# M7102.net
KiCad netlist of a schematic drawn in EAGLE
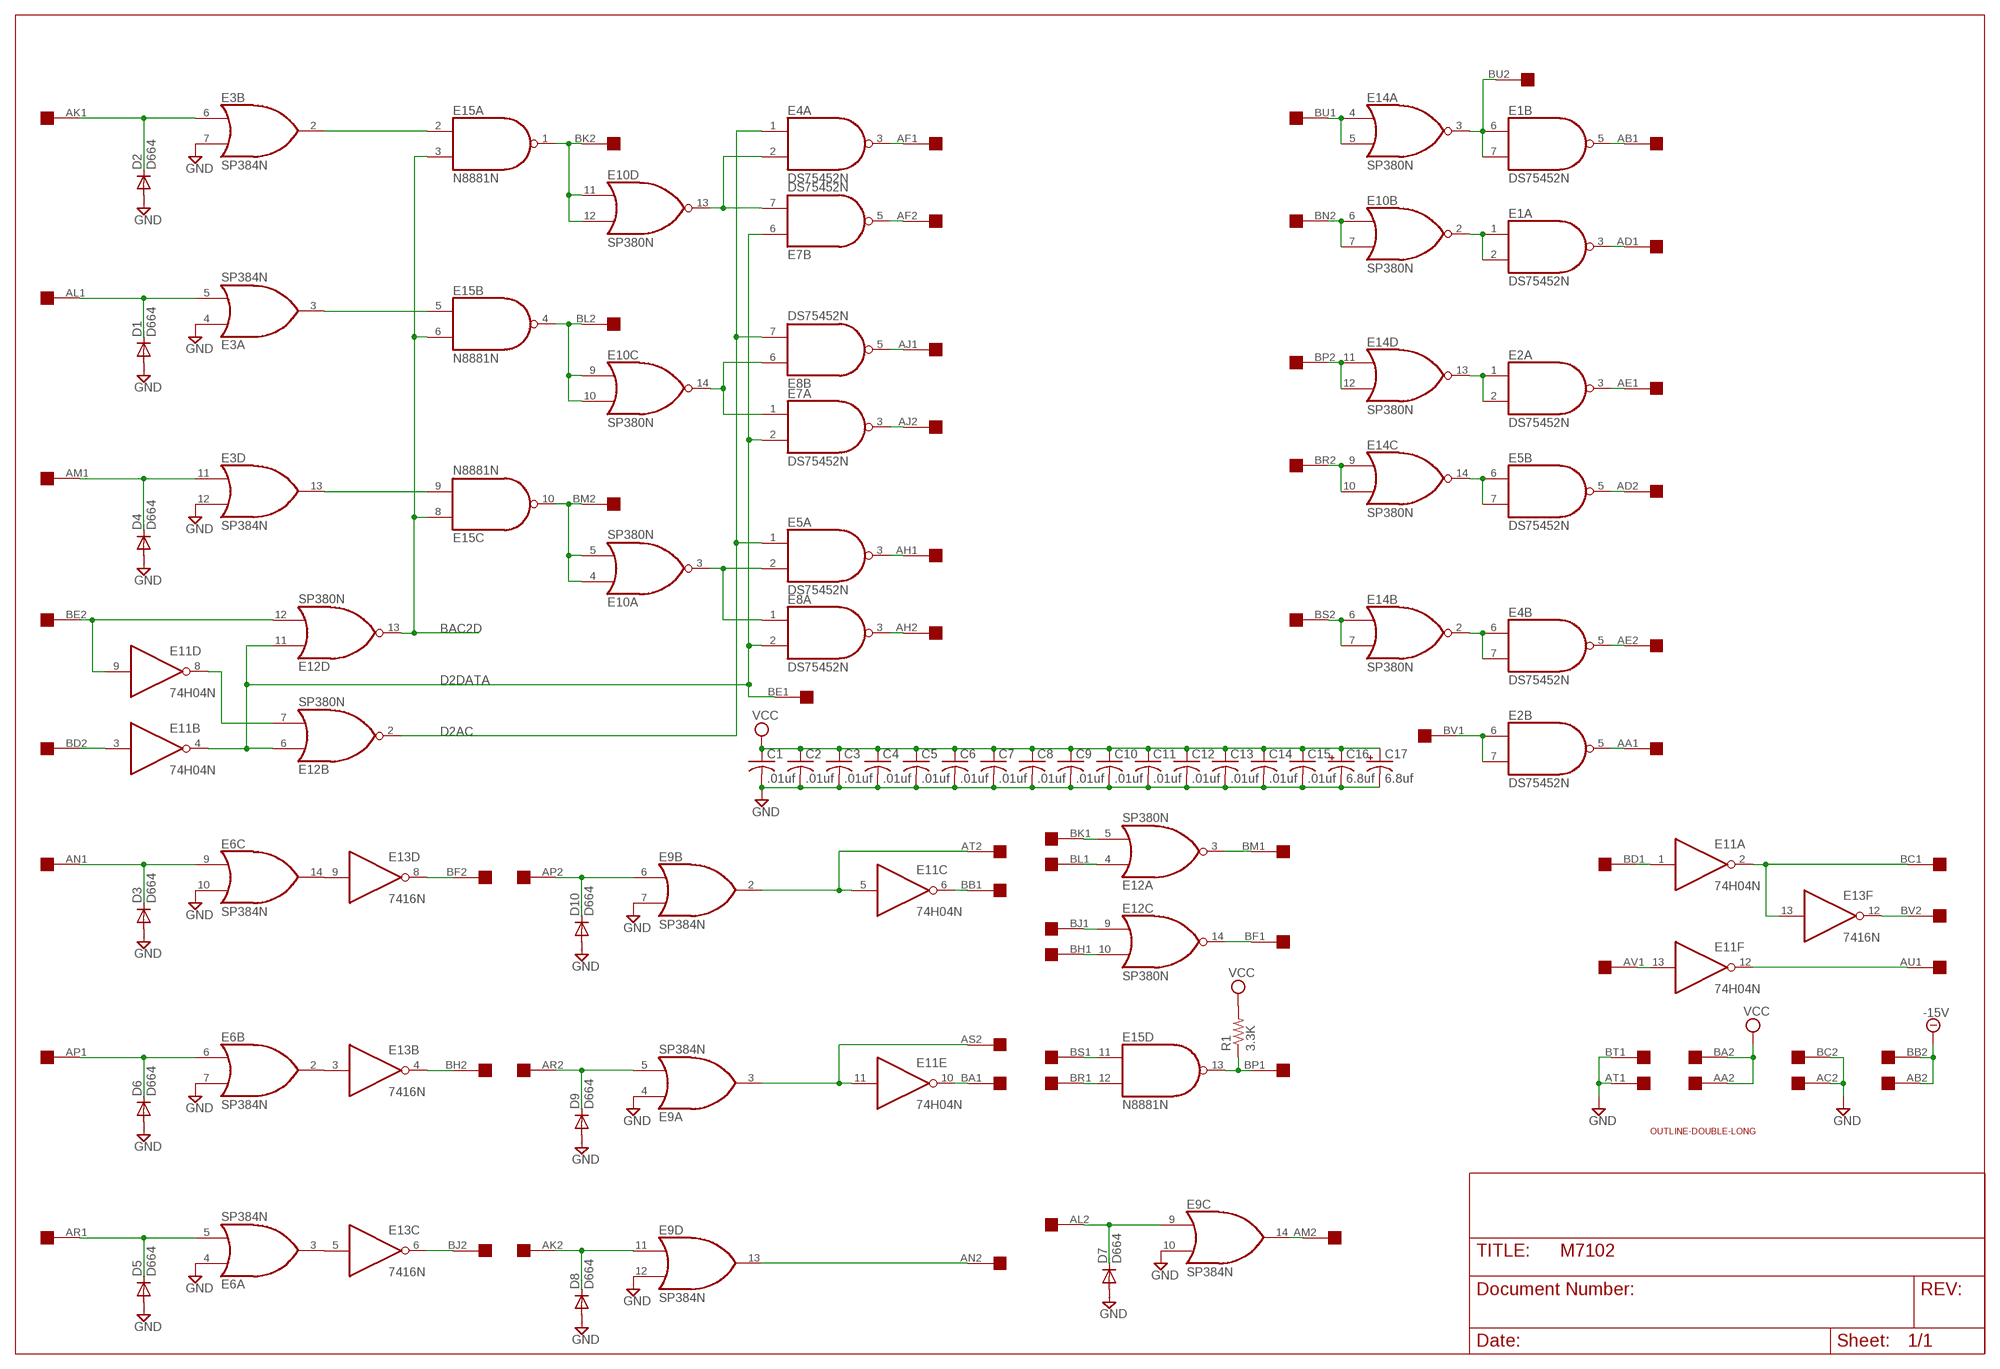
[diagram p0: schematic, sheet 1]

(export (version "E")
  (design (tool "Eeschema 10.0.6"))
  (components
    (comp (ref "C1")
      (value ".01uf")
      (footprint "eagle-import:C050-025X075")
      (libsource (lib "eagle-import") (part "C-US050-025X075"))
    )
    (comp (ref "C2")
      (value ".01uf")
      (footprint "eagle-import:C050-025X075")
      (libsource (lib "eagle-import") (part "C-US050-025X075"))
    )
    (comp (ref "C3")
      (value ".01uf")
      (footprint "eagle-import:C050-025X075")
      (libsource (lib "eagle-import") (part "C-US050-025X075"))
    )
    (comp (ref "C4")
      (value ".01uf")
      (footprint "eagle-import:C050-025X075")
      (libsource (lib "eagle-import") (part "C-US050-025X075"))
    )
    (comp (ref "C5")
      (value ".01uf")
      (footprint "eagle-import:C050-025X075")
      (libsource (lib "eagle-import") (part "C-US050-025X075"))
    )
    (comp (ref "C6")
      (value ".01uf")
      (footprint "eagle-import:C050-025X075")
      (libsource (lib "eagle-import") (part "C-US050-025X075"))
    )
    (comp (ref "C7")
      (value ".01uf")
      (footprint "eagle-import:C050-025X075")
      (libsource (lib "eagle-import") (part "C-US050-025X075"))
    )
    (comp (ref "C8")
      (value ".01uf")
      (footprint "eagle-import:C050-025X075")
      (libsource (lib "eagle-import") (part "C-US050-025X075"))
    )
    (comp (ref "C9")
      (value ".01uf")
      (footprint "eagle-import:C050-025X075")
      (libsource (lib "eagle-import") (part "C-US050-025X075"))
    )
    (comp (ref "C10")
      (value ".01uf")
      (footprint "eagle-import:C050-025X075")
      (libsource (lib "eagle-import") (part "C-US050-025X075"))
    )
    (comp (ref "C11")
      (value ".01uf")
      (footprint "eagle-import:C050-025X075")
      (libsource (lib "eagle-import") (part "C-US050-025X075"))
    )
    (comp (ref "C12")
      (value ".01uf")
      (footprint "eagle-import:C050-025X075")
      (libsource (lib "eagle-import") (part "C-US050-025X075"))
    )
    (comp (ref "C13")
      (value ".01uf")
      (footprint "eagle-import:C050-025X075")
      (libsource (lib "eagle-import") (part "C-US050-025X075"))
    )
    (comp (ref "C14")
      (value ".01uf")
      (footprint "eagle-import:C050-025X075")
      (libsource (lib "eagle-import") (part "C-US050-025X075"))
    )
    (comp (ref "C15")
      (value ".01uf")
      (footprint "eagle-import:C050-025X075")
      (libsource (lib "eagle-import") (part "C-US050-025X075"))
    )
    (comp (ref "C16")
      (value "6.8uf")
      (footprint "eagle-import:E15-5")
      (libsource (lib "eagle-import") (part "CPOL-USE15-5AXIAL"))
    )
    (comp (ref "C17")
      (value "6.8uf")
      (footprint "eagle-import:E15-5")
      (libsource (lib "eagle-import") (part "CPOL-USE15-5AXIAL"))
    )
    (comp (ref "D1")
      (value "D664")
      (footprint "eagle-import:DO35-10")
      (libsource (lib "eagle-import") (part "1N4148DO35-10"))
    )
    (comp (ref "D2")
      (value "D664")
      (footprint "eagle-import:DO35-10")
      (libsource (lib "eagle-import") (part "1N4148DO35-10"))
    )
    (comp (ref "D3")
      (value "D664")
      (footprint "eagle-import:DO35-10")
      (libsource (lib "eagle-import") (part "1N4148DO35-10"))
    )
    (comp (ref "D4")
      (value "D664")
      (footprint "eagle-import:DO35-10")
      (libsource (lib "eagle-import") (part "1N4148DO35-10"))
    )
    (comp (ref "D5")
      (value "D664")
      (footprint "eagle-import:DO35-10")
      (libsource (lib "eagle-import") (part "1N4148DO35-10"))
    )
    (comp (ref "D6")
      (value "D664")
      (footprint "eagle-import:DO35-10")
      (libsource (lib "eagle-import") (part "1N4148DO35-10"))
    )
    (comp (ref "D7")
      (value "D664")
      (footprint "eagle-import:DO35-10")
      (libsource (lib "eagle-import") (part "1N4148DO35-10"))
    )
    (comp (ref "D8")
      (value "D664")
      (footprint "eagle-import:DO35-10")
      (libsource (lib "eagle-import") (part "1N4148DO35-10"))
    )
    (comp (ref "D9")
      (value "D664")
      (footprint "eagle-import:DO35-10")
      (libsource (lib "eagle-import") (part "1N4148DO35-10"))
    )
    (comp (ref "D10")
      (value "D664")
      (footprint "eagle-import:DO35-10")
      (libsource (lib "eagle-import") (part "1N4148DO35-10"))
    )
    (comp (ref "E1")
      (value "DS75452N")
      (footprint "eagle-import:DIL08")
      (libsource (lib "eagle-import") (part "DS75452N"))
    )
    (comp (ref "E2")
      (value "DS75452N")
      (footprint "eagle-import:DIL08")
      (libsource (lib "eagle-import") (part "DS75452N"))
    )
    (comp (ref "E3")
      (value "SP384N")
      (footprint "eagle-import:DIL14")
      (libsource (lib "eagle-import") (part "SP384N"))
    )
    (comp (ref "E4")
      (value "DS75452N")
      (footprint "eagle-import:DIL08")
      (libsource (lib "eagle-import") (part "DS75452N"))
    )
    (comp (ref "E5")
      (value "DS75452N")
      (footprint "eagle-import:DIL08")
      (libsource (lib "eagle-import") (part "DS75452N"))
    )
    (comp (ref "E6")
      (value "SP384N")
      (footprint "eagle-import:DIL14")
      (libsource (lib "eagle-import") (part "SP384N"))
    )
    (comp (ref "E7")
      (value "DS75452N")
      (footprint "eagle-import:DIL08")
      (libsource (lib "eagle-import") (part "DS75452N"))
    )
    (comp (ref "E8")
      (value "DS75452N")
      (footprint "eagle-import:DIL08")
      (libsource (lib "eagle-import") (part "DS75452N"))
    )
    (comp (ref "E9")
      (value "SP384N")
      (footprint "eagle-import:DIL14")
      (libsource (lib "eagle-import") (part "SP384N"))
    )
    (comp (ref "E10")
      (value "SP380N")
      (footprint "eagle-import:DIL14")
      (libsource (lib "eagle-import") (part "SP380N"))
    )
    (comp (ref "E11")
      (value "74H04N")
      (footprint "eagle-import:DIL14")
      (libsource (lib "eagle-import") (part "7404N"))
    )
    (comp (ref "E12")
      (value "SP380N")
      (footprint "eagle-import:DIL14")
      (libsource (lib "eagle-import") (part "SP380N"))
    )
    (comp (ref "E13")
      (value "7416N")
      (footprint "eagle-import:DIL14")
      (libsource (lib "eagle-import") (part "7416N"))
    )
    (comp (ref "E14")
      (value "SP380N")
      (footprint "eagle-import:DIL14")
      (libsource (lib "eagle-import") (part "SP380N"))
    )
    (comp (ref "E15")
      (value "N8881N")
      (footprint "eagle-import:DIL14")
      (libsource (lib "eagle-import") (part "N8881N"))
    )
    (comp (ref "EDGE")
      (value "DOUBLE")
      (footprint "eagle-import:EDGE-CON4")
      (libsource (lib "eagle-import") (part "DOUBLE"))
    )
    (comp (ref "R1")
      (value "3.3K")
      (footprint "eagle-import:0207_10")
      (libsource (lib "eagle-import") (part "R-US_0207/10"))
    )
    (comp (ref "U$3")
      (value "OUTLINE-DOUBLE-LONG")
      (footprint "eagle-import:DOUBLE-LONG")
      (libsource (lib "eagle-import") (part "OUTLINE-DOUBLE-LONG"))
    )
  )
  (nets
    (net (code "1") (name "-15V") (class "Default")
      (node (ref "EDGE") (pin "AB2") (pinfunction "1_AB2") (pintype "bidirectional"))
      (node (ref "EDGE") (pin "BB2") (pinfunction "1_BB2") (pintype "bidirectional"))
    )
    (net (code "2") (name "/BAC2D") (class "Default")
      (node (ref "E12") (pin "13") (pinfunction "O_13") (pintype "output"))
      (node (ref "E15") (pin "3") (pinfunction "I1_3") (pintype "input"))
      (node (ref "E15") (pin "6") (pinfunction "I1_6") (pintype "input"))
      (node (ref "E15") (pin "8") (pinfunction "I0_8") (pintype "input"))
    )
    (net (code "3") (name "/D2AC") (class "Default")
      (node (ref "E12") (pin "2") (pinfunction "O_2") (pintype "output"))
      (node (ref "E4") (pin "1") (pinfunction "I0_1") (pintype "input"))
      (node (ref "E5") (pin "1") (pinfunction "I0_1") (pintype "input"))
      (node (ref "E8") (pin "7") (pinfunction "I1_7") (pintype "input"))
    )
    (net (code "4") (name "/D2DATA") (class "Default")
      (node (ref "E11") (pin "4") (pinfunction "O_4") (pintype "output"))
      (node (ref "E12") (pin "11") (pinfunction "I0_11") (pintype "input"))
      (node (ref "E12") (pin "6") (pinfunction "I0_6") (pintype "input"))
      (node (ref "E7") (pin "2") (pinfunction "I1_2") (pintype "input"))
      (node (ref "E7") (pin "6") (pinfunction "I0_6") (pintype "input"))
      (node (ref "E8") (pin "2") (pinfunction "I1_2") (pintype "input"))
      (node (ref "EDGE") (pin "BE1") (pinfunction "1_BE1") (pintype "bidirectional"))
    )
    (net (code "5") (name "GND") (class "Default")
      (node (ref "C1") (pin "2") (pinfunction "2_2") (pintype "passive"))
      (node (ref "C10") (pin "2") (pinfunction "2_2") (pintype "passive"))
      (node (ref "C11") (pin "2") (pinfunction "2_2") (pintype "passive"))
      (node (ref "C12") (pin "2") (pinfunction "2_2") (pintype "passive"))
      (node (ref "C13") (pin "2") (pinfunction "2_2") (pintype "passive"))
      (node (ref "C14") (pin "2") (pinfunction "2_2") (pintype "passive"))
      (node (ref "C15") (pin "2") (pinfunction "2_2") (pintype "passive"))
      (node (ref "C16") (pin "-") (pinfunction "-_-") (pintype "passive"))
      (node (ref "C17") (pin "-") (pinfunction "-_-") (pintype "passive"))
      (node (ref "C2") (pin "2") (pinfunction "2_2") (pintype "passive"))
      (node (ref "C3") (pin "2") (pinfunction "2_2") (pintype "passive"))
      (node (ref "C4") (pin "2") (pinfunction "2_2") (pintype "passive"))
      (node (ref "C5") (pin "2") (pinfunction "2_2") (pintype "passive"))
      (node (ref "C6") (pin "2") (pinfunction "2_2") (pintype "passive"))
      (node (ref "C7") (pin "2") (pinfunction "2_2") (pintype "passive"))
      (node (ref "C8") (pin "2") (pinfunction "2_2") (pintype "passive"))
      (node (ref "C9") (pin "2") (pinfunction "2_2") (pintype "passive"))
      (node (ref "D1") (pin "A") (pinfunction "A_A") (pintype "passive"))
      (node (ref "D10") (pin "A") (pinfunction "A_A") (pintype "passive"))
      (node (ref "D2") (pin "A") (pinfunction "A_A") (pintype "passive"))
      (node (ref "D3") (pin "A") (pinfunction "A_A") (pintype "passive"))
      (node (ref "D4") (pin "A") (pinfunction "A_A") (pintype "passive"))
      (node (ref "D5") (pin "A") (pinfunction "A_A") (pintype "passive"))
      (node (ref "D6") (pin "A") (pinfunction "A_A") (pintype "passive"))
      (node (ref "D7") (pin "A") (pinfunction "A_A") (pintype "passive"))
      (node (ref "D8") (pin "A") (pinfunction "A_A") (pintype "passive"))
      (node (ref "D9") (pin "A") (pinfunction "A_A") (pintype "passive"))
      (node (ref "E3") (pin "12") (pinfunction "I1_12") (pintype "input"))
      (node (ref "E3") (pin "4") (pinfunction "I0_4") (pintype "input"))
      (node (ref "E3") (pin "7") (pinfunction "I1_7") (pintype "input"))
      (node (ref "E6") (pin "10") (pinfunction "I1_10") (pintype "input"))
      (node (ref "E6") (pin "4") (pinfunction "I0_4") (pintype "input"))
      (node (ref "E6") (pin "7") (pinfunction "I1_7") (pintype "input"))
      (node (ref "E9") (pin "10") (pinfunction "I1_10") (pintype "input"))
      (node (ref "E9") (pin "12") (pinfunction "I1_12") (pintype "input"))
      (node (ref "E9") (pin "4") (pinfunction "I0_4") (pintype "input"))
      (node (ref "E9") (pin "7") (pinfunction "I1_7") (pintype "input"))
      (node (ref "EDGE") (pin "AC2") (pinfunction "1_AC2") (pintype "bidirectional"))
      (node (ref "EDGE") (pin "AT1") (pinfunction "1_AT1") (pintype "bidirectional"))
      (node (ref "EDGE") (pin "BC2") (pinfunction "1_BC2") (pintype "bidirectional"))
      (node (ref "EDGE") (pin "BT1") (pinfunction "1_BT1") (pintype "bidirectional"))
    )
    (net (code "6") (name "Net-(E1A-O)") (class "Default")
      (node (ref "E1") (pin "3") (pinfunction "O_3") (pintype "open_collector"))
      (node (ref "EDGE") (pin "AD1") (pinfunction "1_AD1") (pintype "bidirectional"))
    )
    (net (code "7") (name "Net-(E1B-O)") (class "Default")
      (node (ref "E1") (pin "5") (pinfunction "O_5") (pintype "open_collector"))
      (node (ref "EDGE") (pin "AB1") (pinfunction "1_AB1") (pintype "bidirectional"))
    )
    (net (code "8") (name "Net-(E2A-O)") (class "Default")
      (node (ref "E2") (pin "3") (pinfunction "O_3") (pintype "open_collector"))
      (node (ref "EDGE") (pin "AE1") (pinfunction "1_AE1") (pintype "bidirectional"))
    )
    (net (code "9") (name "Net-(E2B-I0)") (class "Default")
      (node (ref "E2") (pin "6") (pinfunction "I0_6") (pintype "input"))
      (node (ref "E2") (pin "7") (pinfunction "I1_7") (pintype "input"))
      (node (ref "EDGE") (pin "BV1") (pinfunction "1_BV1") (pintype "bidirectional"))
    )
    (net (code "10") (name "Net-(E2B-O)") (class "Default")
      (node (ref "E2") (pin "5") (pinfunction "O_5") (pintype "open_collector"))
      (node (ref "EDGE") (pin "AA1") (pinfunction "1_AA1") (pintype "bidirectional"))
    )
    (net (code "11") (name "Net-(E3A-I1)") (class "Default")
      (node (ref "D1") (pin "C") (pinfunction "C_C") (pintype "passive"))
      (node (ref "E3") (pin "5") (pinfunction "I1_5") (pintype "input"))
      (node (ref "EDGE") (pin "AL1") (pinfunction "1_AL1") (pintype "bidirectional"))
    )
    (net (code "12") (name "Net-(E3B-I0)") (class "Default")
      (node (ref "D2") (pin "C") (pinfunction "C_C") (pintype "passive"))
      (node (ref "E3") (pin "6") (pinfunction "I0_6") (pintype "input"))
      (node (ref "EDGE") (pin "AK1") (pinfunction "1_AK1") (pintype "bidirectional"))
    )
    (net (code "13") (name "Net-(E3D-I0)") (class "Default")
      (node (ref "D4") (pin "C") (pinfunction "C_C") (pintype "passive"))
      (node (ref "E3") (pin "11") (pinfunction "I0_11") (pintype "input"))
      (node (ref "EDGE") (pin "AM1") (pinfunction "1_AM1") (pintype "bidirectional"))
    )
    (net (code "14") (name "Net-(E4A-O)") (class "Default")
      (node (ref "E4") (pin "3") (pinfunction "O_3") (pintype "open_collector"))
      (node (ref "EDGE") (pin "AF1") (pinfunction "1_AF1") (pintype "bidirectional"))
    )
    (net (code "15") (name "Net-(E4B-O)") (class "Default")
      (node (ref "E4") (pin "5") (pinfunction "O_5") (pintype "open_collector"))
      (node (ref "EDGE") (pin "AE2") (pinfunction "1_AE2") (pintype "bidirectional"))
    )
    (net (code "16") (name "Net-(E5A-O)") (class "Default")
      (node (ref "E5") (pin "3") (pinfunction "O_3") (pintype "open_collector"))
      (node (ref "EDGE") (pin "AH1") (pinfunction "1_AH1") (pintype "bidirectional"))
    )
    (net (code "17") (name "Net-(E5B-O)") (class "Default")
      (node (ref "E5") (pin "5") (pinfunction "O_5") (pintype "open_collector"))
      (node (ref "EDGE") (pin "AD2") (pinfunction "1_AD2") (pintype "bidirectional"))
    )
    (net (code "18") (name "Net-(E6A-I1)") (class "Default")
      (node (ref "D5") (pin "C") (pinfunction "C_C") (pintype "passive"))
      (node (ref "E6") (pin "5") (pinfunction "I1_5") (pintype "input"))
      (node (ref "EDGE") (pin "AR1") (pinfunction "1_AR1") (pintype "bidirectional"))
    )
    (net (code "19") (name "Net-(E6B-I0)") (class "Default")
      (node (ref "D6") (pin "C") (pinfunction "C_C") (pintype "passive"))
      (node (ref "E6") (pin "6") (pinfunction "I0_6") (pintype "input"))
      (node (ref "EDGE") (pin "AP1") (pinfunction "1_AP1") (pintype "bidirectional"))
    )
    (net (code "20") (name "Net-(E6C-I0)") (class "Default")
      (node (ref "D3") (pin "C") (pinfunction "C_C") (pintype "passive"))
      (node (ref "E6") (pin "9") (pinfunction "I0_9") (pintype "input"))
      (node (ref "EDGE") (pin "AN1") (pinfunction "1_AN1") (pintype "bidirectional"))
    )
    (net (code "21") (name "Net-(E7A-O)") (class "Default")
      (node (ref "E7") (pin "3") (pinfunction "O_3") (pintype "open_collector"))
      (node (ref "EDGE") (pin "AJ2") (pinfunction "1_AJ2") (pintype "bidirectional"))
    )
    (net (code "22") (name "Net-(E7B-O)") (class "Default")
      (node (ref "E7") (pin "5") (pinfunction "O_5") (pintype "open_collector"))
      (node (ref "EDGE") (pin "AF2") (pinfunction "1_AF2") (pintype "bidirectional"))
    )
    (net (code "23") (name "Net-(E8A-O)") (class "Default")
      (node (ref "E8") (pin "3") (pinfunction "O_3") (pintype "open_collector"))
      (node (ref "EDGE") (pin "AH2") (pinfunction "1_AH2") (pintype "bidirectional"))
    )
    (net (code "24") (name "Net-(E8B-O)") (class "Default")
      (node (ref "E8") (pin "5") (pinfunction "O_5") (pintype "open_collector"))
      (node (ref "EDGE") (pin "AJ1") (pinfunction "1_AJ1") (pintype "bidirectional"))
    )
    (net (code "25") (name "Net-(E9A-I1)") (class "Default")
      (node (ref "D9") (pin "C") (pinfunction "C_C") (pintype "passive"))
      (node (ref "E9") (pin "5") (pinfunction "I1_5") (pintype "input"))
      (node (ref "EDGE") (pin "AR2") (pinfunction "1_AR2") (pintype "bidirectional"))
    )
    (net (code "26") (name "Net-(E9B-I0)") (class "Default")
      (node (ref "D10") (pin "C") (pinfunction "C_C") (pintype "passive"))
      (node (ref "E9") (pin "6") (pinfunction "I0_6") (pintype "input"))
      (node (ref "EDGE") (pin "AP2") (pinfunction "1_AP2") (pintype "bidirectional"))
    )
    (net (code "27") (name "Net-(E9C-I0)") (class "Default")
      (node (ref "D7") (pin "C") (pinfunction "C_C") (pintype "passive"))
      (node (ref "E9") (pin "9") (pinfunction "I0_9") (pintype "input"))
      (node (ref "EDGE") (pin "AL2") (pinfunction "1_AL2") (pintype "bidirectional"))
    )
    (net (code "28") (name "Net-(E9C-O)") (class "Default")
      (node (ref "E9") (pin "14") (pinfunction "O_14") (pintype "output"))
      (node (ref "EDGE") (pin "AM2") (pinfunction "1_AM2") (pintype "bidirectional"))
    )
    (net (code "29") (name "Net-(E9D-I0)") (class "Default")
      (node (ref "D8") (pin "C") (pinfunction "C_C") (pintype "passive"))
      (node (ref "E9") (pin "11") (pinfunction "I0_11") (pintype "input"))
      (node (ref "EDGE") (pin "AK2") (pinfunction "1_AK2") (pintype "bidirectional"))
    )
    (net (code "30") (name "Net-(E9D-O)") (class "Default")
      (node (ref "E9") (pin "13") (pinfunction "O_13") (pintype "output"))
      (node (ref "EDGE") (pin "AN2") (pinfunction "1_AN2") (pintype "bidirectional"))
    )
    (net (code "31") (name "Net-(E10A-I0)") (class "Default")
      (node (ref "E10") (pin "4") (pinfunction "I0_4") (pintype "input"))
      (node (ref "E10") (pin "5") (pinfunction "I1_5") (pintype "input"))
      (node (ref "E15") (pin "10") (pinfunction "O_10") (pintype "open_collector"))
      (node (ref "EDGE") (pin "BM2") (pinfunction "1_BM2") (pintype "bidirectional"))
    )
    (net (code "32") (name "Net-(E10A-O)") (class "Default")
      (node (ref "E10") (pin "3") (pinfunction "O_3") (pintype "output"))
      (node (ref "E5") (pin "2") (pinfunction "I1_2") (pintype "input"))
      (node (ref "E8") (pin "1") (pinfunction "I0_1") (pintype "input"))
    )
    (net (code "33") (name "Net-(E10B-I0)") (class "Default")
      (node (ref "E10") (pin "6") (pinfunction "I0_6") (pintype "input"))
      (node (ref "E10") (pin "7") (pinfunction "I1_7") (pintype "input"))
      (node (ref "EDGE") (pin "BN2") (pinfunction "1_BN2") (pintype "bidirectional"))
    )
    (net (code "34") (name "Net-(E10B-O)") (class "Default")
      (node (ref "E1") (pin "1") (pinfunction "I0_1") (pintype "input"))
      (node (ref "E1") (pin "2") (pinfunction "I1_2") (pintype "input"))
      (node (ref "E10") (pin "2") (pinfunction "O_2") (pintype "output"))
    )
    (net (code "35") (name "Net-(E10C-I0)") (class "Default")
      (node (ref "E10") (pin "10") (pinfunction "I1_10") (pintype "input"))
      (node (ref "E10") (pin "9") (pinfunction "I0_9") (pintype "input"))
      (node (ref "E15") (pin "4") (pinfunction "O_4") (pintype "open_collector"))
      (node (ref "EDGE") (pin "BL2") (pinfunction "1_BL2") (pintype "bidirectional"))
    )
    (net (code "36") (name "Net-(E10C-O)") (class "Default")
      (node (ref "E10") (pin "14") (pinfunction "O_14") (pintype "output"))
      (node (ref "E7") (pin "1") (pinfunction "I0_1") (pintype "input"))
      (node (ref "E8") (pin "6") (pinfunction "I0_6") (pintype "input"))
    )
    (net (code "37") (name "Net-(E10D-I0)") (class "Default")
      (node (ref "E10") (pin "11") (pinfunction "I0_11") (pintype "input"))
      (node (ref "E10") (pin "12") (pinfunction "I1_12") (pintype "input"))
      (node (ref "E15") (pin "1") (pinfunction "O_1") (pintype "open_collector"))
      (node (ref "EDGE") (pin "BK2") (pinfunction "1_BK2") (pintype "bidirectional"))
    )
    (net (code "38") (name "Net-(E10D-O)") (class "Default")
      (node (ref "E10") (pin "13") (pinfunction "O_13") (pintype "output"))
      (node (ref "E4") (pin "2") (pinfunction "I1_2") (pintype "input"))
      (node (ref "E7") (pin "7") (pinfunction "I1_7") (pintype "input"))
    )
    (net (code "39") (name "Net-(E11A-I)") (class "Default")
      (node (ref "E11") (pin "1") (pinfunction "I_1") (pintype "input"))
      (node (ref "EDGE") (pin "BD1") (pinfunction "1_BD1") (pintype "bidirectional"))
    )
    (net (code "40") (name "Net-(E11A-O)") (class "Default")
      (node (ref "E11") (pin "2") (pinfunction "O_2") (pintype "output"))
      (node (ref "E13") (pin "13") (pinfunction "I_13") (pintype "input"))
      (node (ref "EDGE") (pin "BC1") (pinfunction "1_BC1") (pintype "bidirectional"))
    )
    (net (code "41") (name "Net-(E11B-I)") (class "Default")
      (node (ref "E11") (pin "3") (pinfunction "I_3") (pintype "input"))
      (node (ref "EDGE") (pin "BD2") (pinfunction "1_BD2") (pintype "bidirectional"))
    )
    (net (code "42") (name "Net-(E11C-I)") (class "Default")
      (node (ref "E11") (pin "5") (pinfunction "I_5") (pintype "input"))
      (node (ref "E9") (pin "2") (pinfunction "O_2") (pintype "output"))
      (node (ref "EDGE") (pin "AT2") (pinfunction "1_AT2") (pintype "bidirectional"))
    )
    (net (code "43") (name "Net-(E11C-O)") (class "Default")
      (node (ref "E11") (pin "6") (pinfunction "O_6") (pintype "output"))
      (node (ref "EDGE") (pin "BB1") (pinfunction "1_BB1") (pintype "bidirectional"))
    )
    (net (code "44") (name "Net-(E11D-I)") (class "Default")
      (node (ref "E11") (pin "9") (pinfunction "I_9") (pintype "input"))
      (node (ref "E12") (pin "12") (pinfunction "I1_12") (pintype "input"))
      (node (ref "EDGE") (pin "BE2") (pinfunction "1_BE2") (pintype "bidirectional"))
    )
    (net (code "45") (name "Net-(E11D-O)") (class "Default")
      (node (ref "E11") (pin "8") (pinfunction "O_8") (pintype "output"))
      (node (ref "E12") (pin "7") (pinfunction "I1_7") (pintype "input"))
    )
    (net (code "46") (name "Net-(E11E-I)") (class "Default")
      (node (ref "E11") (pin "11") (pinfunction "I_11") (pintype "input"))
      (node (ref "E9") (pin "3") (pinfunction "O_3") (pintype "output"))
      (node (ref "EDGE") (pin "AS2") (pinfunction "1_AS2") (pintype "bidirectional"))
    )
    (net (code "47") (name "Net-(E11E-O)") (class "Default")
      (node (ref "E11") (pin "10") (pinfunction "O_10") (pintype "output"))
      (node (ref "EDGE") (pin "BA1") (pinfunction "1_BA1") (pintype "bidirectional"))
    )
    (net (code "48") (name "Net-(E11F-I)") (class "Default")
      (node (ref "E11") (pin "13") (pinfunction "I_13") (pintype "input"))
      (node (ref "EDGE") (pin "AV1") (pinfunction "1_AV1") (pintype "bidirectional"))
    )
    (net (code "49") (name "Net-(E11F-O)") (class "Default")
      (node (ref "E11") (pin "12") (pinfunction "O_12") (pintype "output"))
      (node (ref "EDGE") (pin "AU1") (pinfunction "1_AU1") (pintype "bidirectional"))
    )
    (net (code "50") (name "Net-(E12A-I0)") (class "Default")
      (node (ref "E12") (pin "4") (pinfunction "I0_4") (pintype "input"))
      (node (ref "EDGE") (pin "BL1") (pinfunction "1_BL1") (pintype "bidirectional"))
    )
    (net (code "51") (name "Net-(E12A-I1)") (class "Default")
      (node (ref "E12") (pin "5") (pinfunction "I1_5") (pintype "input"))
      (node (ref "EDGE") (pin "BK1") (pinfunction "1_BK1") (pintype "bidirectional"))
    )
    (net (code "52") (name "Net-(E12A-O)") (class "Default")
      (node (ref "E12") (pin "3") (pinfunction "O_3") (pintype "output"))
      (node (ref "EDGE") (pin "BM1") (pinfunction "1_BM1") (pintype "bidirectional"))
    )
    (net (code "53") (name "Net-(E12C-I0)") (class "Default")
      (node (ref "E12") (pin "9") (pinfunction "I0_9") (pintype "input"))
      (node (ref "EDGE") (pin "BJ1") (pinfunction "1_BJ1") (pintype "bidirectional"))
    )
    (net (code "54") (name "Net-(E12C-I1)") (class "Default")
      (node (ref "E12") (pin "10") (pinfunction "I1_10") (pintype "input"))
      (node (ref "EDGE") (pin "BH1") (pinfunction "1_BH1") (pintype "bidirectional"))
    )
    (net (code "55") (name "Net-(E12C-O)") (class "Default")
      (node (ref "E12") (pin "14") (pinfunction "O_14") (pintype "output"))
      (node (ref "EDGE") (pin "BF1") (pinfunction "1_BF1") (pintype "bidirectional"))
    )
    (net (code "56") (name "Net-(E13B-I)") (class "Default")
      (node (ref "E13") (pin "3") (pinfunction "I_3") (pintype "input"))
      (node (ref "E6") (pin "2") (pinfunction "O_2") (pintype "output"))
    )
    (net (code "57") (name "Net-(E13B-O)") (class "Default")
      (node (ref "E13") (pin "4") (pinfunction "O_4") (pintype "open_collector"))
      (node (ref "EDGE") (pin "BH2") (pinfunction "1_BH2") (pintype "bidirectional"))
    )
    (net (code "58") (name "Net-(E13C-I)") (class "Default")
      (node (ref "E13") (pin "5") (pinfunction "I_5") (pintype "input"))
      (node (ref "E6") (pin "3") (pinfunction "O_3") (pintype "output"))
    )
    (net (code "59") (name "Net-(E13C-O)") (class "Default")
      (node (ref "E13") (pin "6") (pinfunction "O_6") (pintype "open_collector"))
      (node (ref "EDGE") (pin "BJ2") (pinfunction "1_BJ2") (pintype "bidirectional"))
    )
    (net (code "60") (name "Net-(E13D-I)") (class "Default")
      (node (ref "E13") (pin "9") (pinfunction "I_9") (pintype "input"))
      (node (ref "E6") (pin "14") (pinfunction "O_14") (pintype "output"))
    )
    (net (code "61") (name "Net-(E13D-O)") (class "Default")
      (node (ref "E13") (pin "8") (pinfunction "O_8") (pintype "open_collector"))
      (node (ref "EDGE") (pin "BF2") (pinfunction "1_BF2") (pintype "bidirectional"))
    )
    (net (code "62") (name "Net-(E13F-O)") (class "Default")
      (node (ref "E13") (pin "12") (pinfunction "O_12") (pintype "open_collector"))
      (node (ref "EDGE") (pin "BV2") (pinfunction "1_BV2") (pintype "bidirectional"))
    )
    (net (code "63") (name "Net-(E14A-I0)") (class "Default")
      (node (ref "E14") (pin "4") (pinfunction "I0_4") (pintype "input"))
      (node (ref "E14") (pin "5") (pinfunction "I1_5") (pintype "input"))
      (node (ref "EDGE") (pin "BU1") (pinfunction "1_BU1") (pintype "bidirectional"))
    )
    (net (code "64") (name "Net-(E14A-O)") (class "Default")
      (node (ref "E1") (pin "6") (pinfunction "I0_6") (pintype "input"))
      (node (ref "E1") (pin "7") (pinfunction "I1_7") (pintype "input"))
      (node (ref "E14") (pin "3") (pinfunction "O_3") (pintype "output"))
      (node (ref "EDGE") (pin "BU2") (pinfunction "1_BU2") (pintype "bidirectional"))
    )
    (net (code "65") (name "Net-(E14B-I0)") (class "Default")
      (node (ref "E14") (pin "6") (pinfunction "I0_6") (pintype "input"))
      (node (ref "E14") (pin "7") (pinfunction "I1_7") (pintype "input"))
      (node (ref "EDGE") (pin "BS2") (pinfunction "1_BS2") (pintype "bidirectional"))
    )
    (net (code "66") (name "Net-(E14B-O)") (class "Default")
      (node (ref "E14") (pin "2") (pinfunction "O_2") (pintype "output"))
      (node (ref "E4") (pin "6") (pinfunction "I0_6") (pintype "input"))
      (node (ref "E4") (pin "7") (pinfunction "I1_7") (pintype "input"))
    )
    (net (code "67") (name "Net-(E14C-I0)") (class "Default")
      (node (ref "E14") (pin "10") (pinfunction "I1_10") (pintype "input"))
      (node (ref "E14") (pin "9") (pinfunction "I0_9") (pintype "input"))
      (node (ref "EDGE") (pin "BR2") (pinfunction "1_BR2") (pintype "bidirectional"))
    )
    (net (code "68") (name "Net-(E14C-O)") (class "Default")
      (node (ref "E14") (pin "14") (pinfunction "O_14") (pintype "output"))
      (node (ref "E5") (pin "6") (pinfunction "I0_6") (pintype "input"))
      (node (ref "E5") (pin "7") (pinfunction "I1_7") (pintype "input"))
    )
    (net (code "69") (name "Net-(E14D-I0)") (class "Default")
      (node (ref "E14") (pin "11") (pinfunction "I0_11") (pintype "input"))
      (node (ref "E14") (pin "12") (pinfunction "I1_12") (pintype "input"))
      (node (ref "EDGE") (pin "BP2") (pinfunction "1_BP2") (pintype "bidirectional"))
    )
    (net (code "70") (name "Net-(E14D-O)") (class "Default")
      (node (ref "E14") (pin "13") (pinfunction "O_13") (pintype "output"))
      (node (ref "E2") (pin "1") (pinfunction "I0_1") (pintype "input"))
      (node (ref "E2") (pin "2") (pinfunction "I1_2") (pintype "input"))
    )
    (net (code "71") (name "Net-(E15A-I0)") (class "Default")
      (node (ref "E15") (pin "2") (pinfunction "I0_2") (pintype "input"))
      (node (ref "E3") (pin "2") (pinfunction "O_2") (pintype "output"))
    )
    (net (code "72") (name "Net-(E15B-I0)") (class "Default")
      (node (ref "E15") (pin "5") (pinfunction "I0_5") (pintype "input"))
      (node (ref "E3") (pin "3") (pinfunction "O_3") (pintype "output"))
    )
    (net (code "73") (name "Net-(E15C-I1)") (class "Default")
      (node (ref "E15") (pin "9") (pinfunction "I1_9") (pintype "input"))
      (node (ref "E3") (pin "13") (pinfunction "O_13") (pintype "output"))
    )
    (net (code "74") (name "Net-(E15D-I0)") (class "Default")
      (node (ref "E15") (pin "11") (pinfunction "I0_11") (pintype "input"))
      (node (ref "EDGE") (pin "BS1") (pinfunction "1_BS1") (pintype "bidirectional"))
    )
    (net (code "75") (name "Net-(E15D-I1)") (class "Default")
      (node (ref "E15") (pin "12") (pinfunction "I1_12") (pintype "input"))
      (node (ref "EDGE") (pin "BR1") (pinfunction "1_BR1") (pintype "bidirectional"))
    )
    (net (code "76") (name "Net-(E15D-O)") (class "Default")
      (node (ref "E15") (pin "13") (pinfunction "O_13") (pintype "open_collector"))
      (node (ref "EDGE") (pin "BP1") (pinfunction "1_BP1") (pintype "bidirectional"))
      (node (ref "R1") (pin "1") (pinfunction "1_1") (pintype "passive"))
    )
    (net (code "77") (name "VCC") (class "Default")
      (node (ref "C1") (pin "1") (pinfunction "1_1") (pintype "passive"))
      (node (ref "C10") (pin "1") (pinfunction "1_1") (pintype "passive"))
      (node (ref "C11") (pin "1") (pinfunction "1_1") (pintype "passive"))
      (node (ref "C12") (pin "1") (pinfunction "1_1") (pintype "passive"))
      (node (ref "C13") (pin "1") (pinfunction "1_1") (pintype "passive"))
      (node (ref "C14") (pin "1") (pinfunction "1_1") (pintype "passive"))
      (node (ref "C15") (pin "1") (pinfunction "1_1") (pintype "passive"))
      (node (ref "C16") (pin "+") (pinfunction "+_+") (pintype "passive"))
      (node (ref "C17") (pin "+") (pinfunction "+_+") (pintype "passive"))
      (node (ref "C2") (pin "1") (pinfunction "1_1") (pintype "passive"))
      (node (ref "C3") (pin "1") (pinfunction "1_1") (pintype "passive"))
      (node (ref "C4") (pin "1") (pinfunction "1_1") (pintype "passive"))
      (node (ref "C5") (pin "1") (pinfunction "1_1") (pintype "passive"))
      (node (ref "C6") (pin "1") (pinfunction "1_1") (pintype "passive"))
      (node (ref "C7") (pin "1") (pinfunction "1_1") (pintype "passive"))
      (node (ref "C8") (pin "1") (pinfunction "1_1") (pintype "passive"))
      (node (ref "C9") (pin "1") (pinfunction "1_1") (pintype "passive"))
      (node (ref "EDGE") (pin "AA2") (pinfunction "1_AA2") (pintype "bidirectional"))
      (node (ref "EDGE") (pin "BA2") (pinfunction "1_BA2") (pintype "bidirectional"))
      (node (ref "R1") (pin "2") (pinfunction "2_2") (pintype "passive"))
    )
  )
)
